# masterclock.net
KiCad netlist of a schematic drawn in EAGLE
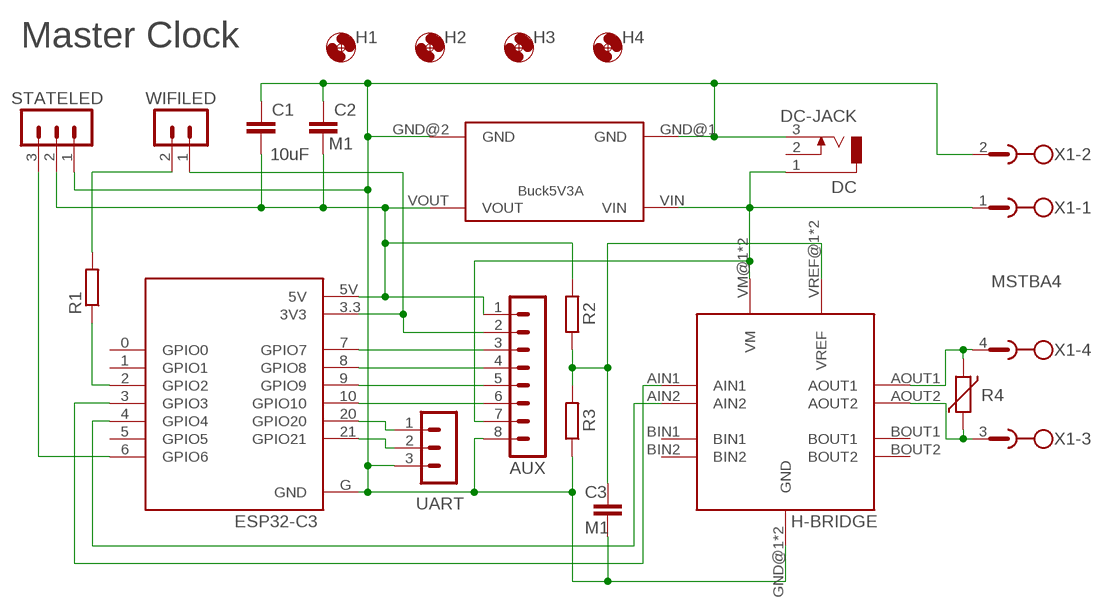
[diagram p0: schematic, sheet 1]

(export (version "E")
  (design (tool "Eeschema 10.0.6"))
  (components
    (comp (ref "AUX")
      (value "CON-LSTB_MA08-108")
      (footprint "eagle-import:CON-LSTB-MA08-1-NS08")
      (libsource (lib "eagle-import") (part "CON-LSTB_MA08-108"))
    )
    (comp (ref "C1")
      (value "10uF")
      (footprint "eagle-import:C1206")
      (libsource (lib "eagle-import") (part "C-EUC1206"))
    )
    (comp (ref "C2")
      (value "M1")
      (footprint "eagle-import:C0805")
      (libsource (lib "eagle-import") (part "C-EUC0805"))
    )
    (comp (ref "C3")
      (value "M1")
      (footprint "eagle-import:C0805")
      (libsource (lib "eagle-import") (part "C-EUC0805"))
    )
    (comp (ref "DC")
      (value "DC-JACK")
      (footprint "eagle-import:DCJ0202")
      (libsource (lib "eagle-import") (part "DC-JACK"))
    )
    (comp (ref "ESP32-C3")
      (value "ESP32-C3_SUPERMINI")
      (footprint "eagle-import:ESP32-C3_SUPERMINI_MODULE_ESP32-C3_SUPERMINI")
      (libsource (lib "eagle-import") (part "ESP32-C3_SUPERMINI"))
    )
    (comp (ref "H-BRIDGE")
      (value "A4950_MODULE")
      (footprint "eagle-import:A4950_MODULE")
      (libsource (lib "eagle-import") (part "A4950_MODULE"))
    )
    (comp (ref "H1")
      (value "MOUNT-HOLE3,0-2,5")
      (footprint "eagle-import:3,0-2,5")
      (libsource (lib "eagle-import") (part "MOUNT-HOLE3,0-2,5"))
    )
    (comp (ref "H2")
      (value "MOUNT-HOLE3,0-2,5")
      (footprint "eagle-import:3,0-2,5")
      (libsource (lib "eagle-import") (part "MOUNT-HOLE3,0-2,5"))
    )
    (comp (ref "H3")
      (value "MOUNT-HOLE3,0-2,5")
      (footprint "eagle-import:3,0-2,5")
      (libsource (lib "eagle-import") (part "MOUNT-HOLE3,0-2,5"))
    )
    (comp (ref "H4")
      (value "MOUNT-HOLE3,0-2,5")
      (footprint "eagle-import:3,0-2,5")
      (libsource (lib "eagle-import") (part "MOUNT-HOLE3,0-2,5"))
    )
    (comp (ref "R1")
      (value "R-EU_R0805")
      (footprint "eagle-import:R0805")
      (libsource (lib "eagle-import") (part "R-EU_R0805"))
    )
    (comp (ref "R2")
      (value "R-EU_R0805")
      (footprint "eagle-import:R0805")
      (libsource (lib "eagle-import") (part "R-EU_R0805"))
    )
    (comp (ref "R3")
      (value "R-EU_R0805")
      (footprint "eagle-import:R0805")
      (libsource (lib "eagle-import") (part "R-EU_R0805"))
    )
    (comp (ref "R4")
      (value "VARISTORS07KS07K385")
      (footprint "eagle-import:S07K385")
      (libsource (lib "eagle-import") (part "VARISTORS07KS07K385"))
    )
    (comp (ref "STATELED")
      (value "CON-LSTB_MA03-108")
      (footprint "eagle-import:CON-LSTB_MA03-1-NS08")
      (libsource (lib "eagle-import") (part "CON-LSTB_MA03-108"))
    )
    (comp (ref "U$3")
      (value "BUCK5V3A")
      (footprint "eagle-import:BUCK5V3A")
      (libsource (lib "eagle-import") (part "BUCK5V3A"))
    )
    (comp (ref "UART")
      (value "CON-LSTB_MA03-108")
      (footprint "eagle-import:CON-LSTB_MA03-1-NS08")
      (libsource (lib "eagle-import") (part "CON-LSTB_MA03-108"))
    )
    (comp (ref "WIFILED")
      (value "CON-LSTB_MA02-1NS08")
      (footprint "eagle-import:CON-LSTB_MA02-1-NS08")
      (libsource (lib "eagle-import") (part "CON-LSTB_MA02-1NS08"))
    )
    (comp (ref "X1")
      (value "MSTBA4")
      (footprint "eagle-import:MSTBA4")
      (fields (field (name "MF") "FARNELL") (field (name "MPN") "1757268"))
      (libsource (lib "eagle-import") (part "MSTBA4"))
    )
  )
  (nets
    (net (code "1") (name "Net-(AUX-Pad1)") (class "Default")
      (node (ref "AUX") (pin "1") (pinfunction "1_1") (pintype "passive"))
      (node (ref "C1") (pin "2") (pinfunction "2_2") (pintype "passive"))
      (node (ref "C2") (pin "2") (pinfunction "2_2") (pintype "passive"))
      (node (ref "ESP32-C3") (pin "5V") (pinfunction "5V_5V") (pintype "power_in"))
      (node (ref "R2") (pin "2") (pinfunction "2_2") (pintype "passive"))
      (node (ref "STATELED") (pin "2") (pinfunction "2_2") (pintype "passive"))
      (node (ref "U$3") (pin "VOUT") (pinfunction "VOUT_VOUT") (pintype "power_in"))
    )
    (net (code "2") (name "Net-(AUX-Pad7)") (class "Default")
      (node (ref "AUX") (pin "7") (pinfunction "7_7") (pintype "passive"))
      (node (ref "DC") (pin "1") (pinfunction "1_1") (pintype "passive"))
      (node (ref "H-BRIDGE") (pin "VM@1") (pinfunction "VM_VM@1") (pintype "power_in"))
      (node (ref "H-BRIDGE") (pin "VM@2") (pinfunction "VM_VM@2") (pintype "power_in"))
      (node (ref "U$3") (pin "VIN") (pinfunction "VIN_VIN") (pintype "power_in"))
      (node (ref "X1") (pin "1") (pinfunction "1_1") (pintype "passive"))
    )
    (net (code "3") (name "Net-(C3-Pad1)") (class "Default")
      (node (ref "C3") (pin "1") (pinfunction "1_1") (pintype "passive"))
      (node (ref "H-BRIDGE") (pin "VREF@1") (pinfunction "VREF_VREF@1") (pintype "power_in"))
      (node (ref "H-BRIDGE") (pin "VREF@2") (pinfunction "VREF_VREF@2") (pintype "power_in"))
      (node (ref "R2") (pin "1") (pinfunction "1_1") (pintype "passive"))
      (node (ref "R3") (pin "2") (pinfunction "2_2") (pintype "passive"))
    )
    (net (code "4") (name "Net-(ESP32-C3-3V3)") (class "Default")
      (node (ref "AUX") (pin "2") (pinfunction "2_2") (pintype "passive"))
      (node (ref "ESP32-C3") (pin "3.3") (pinfunction "3V3_3.3") (pintype "power_in"))
      (node (ref "WIFILED") (pin "1") (pinfunction "1_1") (pintype "passive"))
    )
    (net (code "5") (name "Net-(ESP32-C3-GND)") (class "Default")
      (node (ref "AUX") (pin "8") (pinfunction "8_8") (pintype "passive"))
      (node (ref "C1") (pin "1") (pinfunction "1_1") (pintype "passive"))
      (node (ref "C2") (pin "1") (pinfunction "1_1") (pintype "passive"))
      (node (ref "C3") (pin "2") (pinfunction "2_2") (pintype "passive"))
      (node (ref "DC") (pin "3") (pinfunction "3_3") (pintype "passive"))
      (node (ref "ESP32-C3") (pin "G") (pinfunction "GND_G") (pintype "power_in"))
      (node (ref "H-BRIDGE") (pin "GND@1") (pinfunction "GND_GND@1") (pintype "power_in"))
      (node (ref "H-BRIDGE") (pin "GND@2") (pinfunction "GND_GND@2") (pintype "power_in"))
      (node (ref "R3") (pin "1") (pinfunction "1_1") (pintype "passive"))
      (node (ref "STATELED") (pin "1") (pinfunction "1_1") (pintype "passive"))
      (node (ref "U$3") (pin "GND@1") (pinfunction "GND_GND@1") (pintype "power_in"))
      (node (ref "U$3") (pin "GND@2") (pinfunction "GND_GND@2") (pintype "power_in"))
      (node (ref "UART") (pin "3") (pinfunction "3_3") (pintype "passive"))
      (node (ref "X1") (pin "2") (pinfunction "1_2") (pintype "passive"))
    )
    (net (code "6") (name "Net-(ESP32-C3-GPIO2)") (class "Default")
      (node (ref "ESP32-C3") (pin "2") (pinfunction "GPIO2_2") (pintype "bidirectional"))
      (node (ref "R1") (pin "1") (pinfunction "1_1") (pintype "passive"))
    )
    (net (code "7") (name "Net-(ESP32-C3-GPIO3)") (class "Default")
      (node (ref "ESP32-C3") (pin "3") (pinfunction "GPIO3_3") (pintype "bidirectional"))
      (node (ref "H-BRIDGE") (pin "AIN1") (pinfunction "AIN1_AIN1") (pintype "input"))
    )
    (net (code "8") (name "Net-(ESP32-C3-GPIO4)") (class "Default")
      (node (ref "ESP32-C3") (pin "4") (pinfunction "GPIO4_4") (pintype "bidirectional"))
      (node (ref "H-BRIDGE") (pin "AIN2") (pinfunction "AIN2_AIN2") (pintype "input"))
    )
    (net (code "9") (name "Net-(ESP32-C3-GPIO6)") (class "Default")
      (node (ref "ESP32-C3") (pin "6") (pinfunction "GPIO6_6") (pintype "bidirectional"))
      (node (ref "STATELED") (pin "3") (pinfunction "3_3") (pintype "passive"))
    )
    (net (code "10") (name "Net-(ESP32-C3-GPIO7)") (class "Default")
      (node (ref "AUX") (pin "3") (pinfunction "3_3") (pintype "passive"))
      (node (ref "ESP32-C3") (pin "7") (pinfunction "GPIO7_7") (pintype "bidirectional"))
    )
    (net (code "11") (name "Net-(ESP32-C3-GPIO8)") (class "Default")
      (node (ref "AUX") (pin "4") (pinfunction "4_4") (pintype "passive"))
      (node (ref "ESP32-C3") (pin "8") (pinfunction "GPIO8_8") (pintype "bidirectional"))
    )
    (net (code "12") (name "Net-(ESP32-C3-GPIO9)") (class "Default")
      (node (ref "AUX") (pin "5") (pinfunction "5_5") (pintype "passive"))
      (node (ref "ESP32-C3") (pin "9") (pinfunction "GPIO9_9") (pintype "bidirectional"))
    )
    (net (code "13") (name "Net-(ESP32-C3-GPIO10)") (class "Default")
      (node (ref "AUX") (pin "6") (pinfunction "6_6") (pintype "passive"))
      (node (ref "ESP32-C3") (pin "10") (pinfunction "GPIO10_10") (pintype "bidirectional"))
    )
    (net (code "14") (name "Net-(ESP32-C3-GPIO20)") (class "Default")
      (node (ref "ESP32-C3") (pin "20") (pinfunction "GPIO20_20") (pintype "bidirectional"))
      (node (ref "UART") (pin "1") (pinfunction "1_1") (pintype "passive"))
    )
    (net (code "15") (name "Net-(ESP32-C3-GPIO21)") (class "Default")
      (node (ref "ESP32-C3") (pin "21") (pinfunction "GPIO21_21") (pintype "bidirectional"))
      (node (ref "UART") (pin "2") (pinfunction "2_2") (pintype "passive"))
    )
    (net (code "16") (name "Net-(R1-Pad2)") (class "Default")
      (node (ref "R1") (pin "2") (pinfunction "2_2") (pintype "passive"))
      (node (ref "WIFILED") (pin "2") (pinfunction "2_2") (pintype "passive"))
    )
    (net (code "17") (name "Net-(X1C-1)") (class "Default")
      (node (ref "H-BRIDGE") (pin "AOUT2") (pinfunction "AOUT2_AOUT2") (pintype "output"))
      (node (ref "R4") (pin "1") (pinfunction "1_1") (pintype "passive"))
      (node (ref "X1") (pin "3") (pinfunction "1_3") (pintype "passive"))
    )
    (net (code "18") (name "Net-(X1D-1)") (class "Default")
      (node (ref "H-BRIDGE") (pin "AOUT1") (pinfunction "AOUT1_AOUT1") (pintype "output"))
      (node (ref "R4") (pin "2") (pinfunction "2_2") (pintype "passive"))
      (node (ref "X1") (pin "4") (pinfunction "1_4") (pintype "passive"))
    )
    (net (code "19") (name "unconnected-(DC-Pad2)") (class "Default")
      (node (ref "DC") (pin "2") (pinfunction "2_2") (pintype "passive"))
    )
    (net (code "20") (name "unconnected-(ESP32-C3-GPIO0-Pad0)") (class "Default")
      (node (ref "ESP32-C3") (pin "0") (pinfunction "GPIO0_0") (pintype "bidirectional"))
    )
    (net (code "21") (name "unconnected-(ESP32-C3-GPIO1-Pad1)") (class "Default")
      (node (ref "ESP32-C3") (pin "1") (pinfunction "GPIO1_1") (pintype "bidirectional"))
    )
    (net (code "22") (name "unconnected-(ESP32-C3-GPIO5-Pad5)") (class "Default")
      (node (ref "ESP32-C3") (pin "5") (pinfunction "GPIO5_5") (pintype "bidirectional"))
    )
    (net (code "23") (name "unconnected-(H-BRIDGE-PadBIN1)") (class "Default")
      (node (ref "H-BRIDGE") (pin "BIN1") (pinfunction "BIN1_BIN1") (pintype "input"))
    )
    (net (code "24") (name "unconnected-(H-BRIDGE-PadBIN2)") (class "Default")
      (node (ref "H-BRIDGE") (pin "BIN2") (pinfunction "BIN2_BIN2") (pintype "input"))
    )
    (net (code "25") (name "unconnected-(H-BRIDGE-PadBOUT1)") (class "Default")
      (node (ref "H-BRIDGE") (pin "BOUT1") (pinfunction "BOUT1_BOUT1") (pintype "output"))
    )
    (net (code "26") (name "unconnected-(H-BRIDGE-PadBOUT2)") (class "Default")
      (node (ref "H-BRIDGE") (pin "BOUT2") (pinfunction "BOUT2_BOUT2") (pintype "output"))
    )
  )
)
